# dianji.net
KiCad netlist of a schematic drawn in Altium Designer
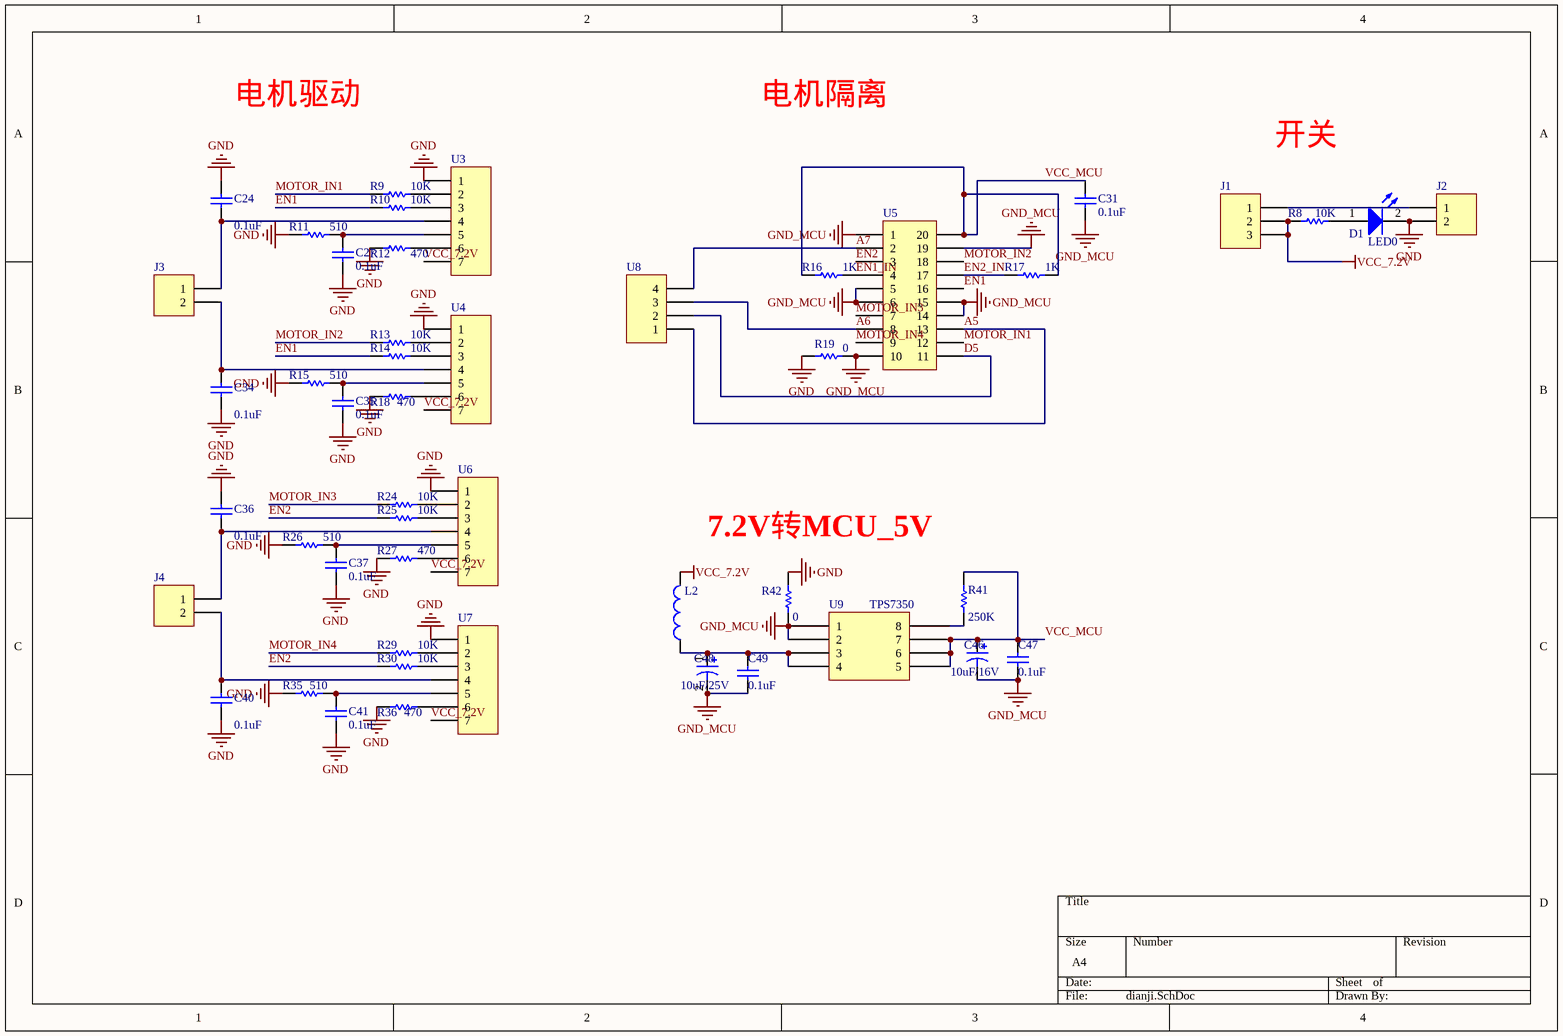
[diagram p0: dianji.SchDoc]

(export (version "E")
  (design (tool "Eeschema 10.0.6"))
  (components
    (comp (ref "C24")
      (value "0.1uF")
      (footprint "C0805")
      (description "Capacitor")
      (fields (field (name "PUBLISHER") "Altium Limited"))
      (libsource (lib "Miscellaneous Devices") (part "Cap"))
    )
    (comp (ref "C27")
      (value "0.1uF")
      (footprint "C0805")
      (description "Capacitor")
      (fields (field (name "PUBLISHER") "Altium Limited"))
      (libsource (lib "Miscellaneous Devices") (part "Cap"))
    )
    (comp (ref "C31")
      (value "0.1uF")
      (footprint "C0805")
      (description "Capacitor")
      (fields (field (name "PUBLISHER") "Altium Limited"))
      (libsource (lib "Miscellaneous Devices") (part "Cap"))
    )
    (comp (ref "C34")
      (value "0.1uF")
      (footprint "C0805")
      (description "Capacitor")
      (fields (field (name "PUBLISHER") "Altium Limited"))
      (libsource (lib "Miscellaneous Devices") (part "Cap"))
    )
    (comp (ref "C35")
      (value "0.1uF")
      (footprint "C0805")
      (description "Capacitor")
      (fields (field (name "PUBLISHER") "Altium Limited"))
      (libsource (lib "Miscellaneous Devices") (part "Cap"))
    )
    (comp (ref "C36")
      (value "0.1uF")
      (footprint "C0805")
      (description "Capacitor")
      (fields (field (name "PUBLISHER") "Altium Limited"))
      (libsource (lib "Miscellaneous Devices") (part "Cap"))
    )
    (comp (ref "C37")
      (value "0.1uF")
      (footprint "C0805")
      (description "Capacitor")
      (fields (field (name "PUBLISHER") "Altium Limited"))
      (libsource (lib "Miscellaneous Devices") (part "Cap"))
    )
    (comp (ref "C40")
      (value "0.1uF")
      (footprint "C0805")
      (description "Capacitor")
      (fields (field (name "PUBLISHER") "Altium Limited"))
      (libsource (lib "Miscellaneous Devices") (part "Cap"))
    )
    (comp (ref "C41")
      (value "0.1uF")
      (footprint "C0805")
      (description "Capacitor")
      (fields (field (name "PUBLISHER") "Altium Limited"))
      (libsource (lib "Miscellaneous Devices") (part "Cap"))
    )
    (comp (ref "C46")
      (value "10uF/16V")
      (footprint "C1206")
      (description "Polarized Capacitor (Radial)")
      (fields (field (name "PUBLISHER") "Altium Limited"))
      (libsource (lib "Miscellaneous Devices") (part "Cap Pol1"))
    )
    (comp (ref "C47")
      (value "0.1uF")
      (footprint "C0805")
      (description "Capacitor")
      (fields (field (name "PUBLISHER") "Altium Limited"))
      (libsource (lib "Miscellaneous Devices") (part "Cap"))
    )
    (comp (ref "C48")
      (value "10uF/25V")
      (footprint "C1206")
      (description "Polarized Capacitor (Radial)")
      (fields (field (name "PUBLISHER") "Altium Limited"))
      (libsource (lib "") (part "Cap Pol1_1"))
    )
    (comp (ref "C49")
      (value "0.1uF")
      (footprint "C0805")
      (description "Capacitor")
      (fields (field (name "PUBLISHER") "Altium Limited"))
      (libsource (lib "Miscellaneous Devices") (part "Cap"))
    )
    (comp (ref "D1")
      (value "LED0")
      (footprint "d0603")
      (description "Typical INFRARED GaAs LED")
      (fields (field (name "PUBLISHER") "Altium Limited"))
      (libsource (lib "Miscellaneous Devices") (part "LED0"))
    )
    (comp (ref "J1")
      (value "Header 3")
      (footprint "7.2")
      (description "Header, 3-Pin")
      (fields (field (name "PUBLISHER") "Altium Limited"))
      (libsource (lib "Miscellaneous Connectors") (part "Header 3"))
    )
    (comp (ref "J2")
      (value "Header 2")
      (footprint "PCBComponent_1 - duplicate5")
      (description "Header, 2-Pin")
      (fields (field (name "PUBLISHER") "Altium Limited"))
      (libsource (lib "") (part "Header 2_1"))
    )
    (comp (ref "J3")
      (value "Header 2")
      (footprint "1")
      (description "Header, 2-Pin")
      (fields (field (name "PUBLISHER") "Altium Limited"))
      (libsource (lib "Miscellaneous Connectors") (part "Header 2"))
    )
    (comp (ref "J4")
      (value "Header 2")
      (footprint "1")
      (description "Header, 2-Pin")
      (fields (field (name "PUBLISHER") "Altium Limited"))
      (libsource (lib "Miscellaneous Connectors") (part "Header 2"))
    )
    (comp (ref "L2")
      (value "~")
      (footprint "L0805")
      (description "Inductor")
      (fields (field (name "PUBLISHER") "Altium Limited"))
      (libsource (lib "Miscellaneous Devices") (part "Inductor"))
    )
    (comp (ref "R8")
      (value "10K")
      (footprint "R0805")
      (description "Resistor")
      (fields (field (name "Comment") "Res1") (field (name "PUBLISHER") "Altium Limited"))
      (libsource (lib "Miscellaneous Devices") (part "Res1"))
    )
    (comp (ref "R9")
      (value "10K")
      (footprint "R0805")
      (description "Resistor")
      (fields (field (name "PUBLISHER") "Altium Limited"))
      (libsource (lib "Miscellaneous Devices") (part "Res1"))
    )
    (comp (ref "R10")
      (value "10K")
      (footprint "R0805")
      (description "Resistor")
      (fields (field (name "PUBLISHER") "Altium Limited"))
      (libsource (lib "Miscellaneous Devices") (part "Res1"))
    )
    (comp (ref "R11")
      (value "510")
      (footprint "R0805")
      (description "Resistor")
      (fields (field (name "Comment") "510R") (field (name "PUBLISHER") "Altium Limited"))
      (libsource (lib "Miscellaneous Devices") (part "Res1"))
    )
    (comp (ref "R12")
      (value "470")
      (footprint "R0805")
      (description "Resistor")
      (fields (field (name "Comment") "470R") (field (name "PUBLISHER") "Altium Limited"))
      (libsource (lib "Miscellaneous Devices") (part "Res1"))
    )
    (comp (ref "R13")
      (value "10K")
      (footprint "R0805")
      (description "Resistor")
      (fields (field (name "PUBLISHER") "Altium Limited"))
      (libsource (lib "Miscellaneous Devices") (part "Res1"))
    )
    (comp (ref "R14")
      (value "10K")
      (footprint "R0805")
      (description "Resistor")
      (fields (field (name "Comment") "Res1") (field (name "PUBLISHER") "Altium Limited"))
      (libsource (lib "Miscellaneous Devices") (part "Res1"))
    )
    (comp (ref "R15")
      (value "510")
      (footprint "R0805")
      (description "Resistor")
      (fields (field (name "Comment") "510R") (field (name "PUBLISHER") "Altium Limited"))
      (libsource (lib "Miscellaneous Devices") (part "Res1"))
    )
    (comp (ref "R16")
      (value "1K")
      (footprint "R0805")
      (description "Resistor")
      (fields (field (name "PUBLISHER") "Altium Limited"))
      (libsource (lib "Miscellaneous Devices") (part "Res1"))
    )
    (comp (ref "R17")
      (value "1K")
      (footprint "R0805")
      (description "Resistor")
      (fields (field (name "PUBLISHER") "Altium Limited"))
      (libsource (lib "Miscellaneous Devices") (part "Res1"))
    )
    (comp (ref "R18")
      (value "470")
      (footprint "R0805")
      (description "Resistor")
      (fields (field (name "Comment") "470R") (field (name "PUBLISHER") "Altium Limited"))
      (libsource (lib "Miscellaneous Devices") (part "Res1"))
    )
    (comp (ref "R19")
      (value "0")
      (footprint "R0805")
      (description "Resistor")
      (fields (field (name "PUBLISHER") "Altium Limited"))
      (libsource (lib "Miscellaneous Devices") (part "Res1"))
    )
    (comp (ref "R24")
      (value "10K")
      (footprint "R0805")
      (description "Resistor")
      (fields (field (name "PUBLISHER") "Altium Limited"))
      (libsource (lib "Miscellaneous Devices") (part "Res1"))
    )
    (comp (ref "R25")
      (value "10K")
      (footprint "R0805")
      (description "Resistor")
      (fields (field (name "PUBLISHER") "Altium Limited"))
      (libsource (lib "Miscellaneous Devices") (part "Res1"))
    )
    (comp (ref "R26")
      (value "510")
      (footprint "R0805")
      (description "Resistor")
      (fields (field (name "Comment") "510R") (field (name "PUBLISHER") "Altium Limited"))
      (libsource (lib "Miscellaneous Devices") (part "Res1"))
    )
    (comp (ref "R27")
      (value "470")
      (footprint "R0805")
      (description "Resistor")
      (fields (field (name "Comment") "470R") (field (name "PUBLISHER") "Altium Limited"))
      (libsource (lib "Miscellaneous Devices") (part "Res1"))
    )
    (comp (ref "R29")
      (value "10K")
      (footprint "R0805")
      (description "Resistor")
      (fields (field (name "PUBLISHER") "Altium Limited"))
      (libsource (lib "Miscellaneous Devices") (part "Res1"))
    )
    (comp (ref "R30")
      (value "10K")
      (footprint "R0805")
      (description "Resistor")
      (fields (field (name "PUBLISHER") "Altium Limited"))
      (libsource (lib "Miscellaneous Devices") (part "Res1"))
    )
    (comp (ref "R35")
      (value "510")
      (footprint "R0805")
      (description "Resistor")
      (fields (field (name "Comment") "510R") (field (name "PUBLISHER") "Altium Limited"))
      (libsource (lib "Miscellaneous Devices") (part "Res1"))
    )
    (comp (ref "R36")
      (value "470")
      (footprint "R0805")
      (description "Resistor")
      (fields (field (name "Comment") "470R") (field (name "PUBLISHER") "Altium Limited"))
      (libsource (lib "Miscellaneous Devices") (part "Res1"))
    )
    (comp (ref "R41")
      (value "250K")
      (footprint "R0805")
      (description "Resistor")
      (fields (field (name "PUBLISHER") "Altium Limited"))
      (libsource (lib "Miscellaneous Devices") (part "Res1"))
    )
    (comp (ref "R42")
      (value "0")
      (footprint "R0805")
      (description "Resistor")
      (fields (field (name "PUBLISHER") "Altium Limited"))
      (libsource (lib "Miscellaneous Devices") (part "Res1"))
    )
    (comp (ref "U3")
      (value "Header 7")
      (footprint "BST7970")
      (description "Header, 7-Pin")
      (fields (field (name "PUBLISHER") "Altium Limited"))
      (libsource (lib "Miscellaneous Connectors") (part "Header 7"))
    )
    (comp (ref "U4")
      (value "Header 7")
      (footprint "BST7970")
      (description "Header, 7-Pin")
      (fields (field (name "PUBLISHER") "Altium Limited"))
      (libsource (lib "Miscellaneous Connectors") (part "Header 7"))
    )
    (comp (ref "U5")
      (value "Header 10X2")
      (footprint "xin")
      (description "Header, 10-Pin, Dual row")
      (fields (field (name "PUBLISHER") "Altium Limited"))
      (libsource (lib "Miscellaneous Connectors") (part "Header 10X2"))
    )
    (comp (ref "U6")
      (value "Header 7")
      (footprint "BST7970")
      (description "Header, 7-Pin")
      (fields (field (name "PUBLISHER") "Altium Limited"))
      (libsource (lib "Miscellaneous Connectors") (part "Header 7"))
    )
    (comp (ref "U7")
      (value "Header 7")
      (footprint "BST7970")
      (description "Header, 7-Pin")
      (fields (field (name "PUBLISHER") "Altium Limited"))
      (libsource (lib "Miscellaneous Connectors") (part "Header 7"))
    )
    (comp (ref "U8")
      (value "Header 4")
      (footprint "SIP4")
      (description "Header, 4-Pin")
      (fields (field (name "PUBLISHER") "Altium Limited"))
      (libsource (lib "Miscellaneous Connectors") (part "Header 4"))
    )
    (comp (ref "U9") (value "TPS7350") (footprint "sop8") (libsource (lib "Schlib1") (part "Component_1")))
  )
  (nets
    (net (code "1") (name "/A5") (class "Default")
      (node (ref "U5") (pin "13") (pinfunction "13_13") (pintype "passive"))
      (node (ref "U8") (pin "1") (pinfunction "1_1") (pintype "passive"))
    )
    (net (code "2") (name "/A6") (class "Default")
      (node (ref "U5") (pin "8") (pinfunction "8_8") (pintype "passive"))
      (node (ref "U8") (pin "3") (pinfunction "3_3") (pintype "passive"))
    )
    (net (code "3") (name "/A7") (class "Default")
      (node (ref "U5") (pin "2") (pinfunction "2_2") (pintype "passive"))
      (node (ref "U8") (pin "4") (pinfunction "4_4") (pintype "passive"))
    )
    (net (code "4") (name "/D5") (class "Default")
      (node (ref "U5") (pin "11") (pinfunction "11_11") (pintype "passive"))
      (node (ref "U8") (pin "2") (pinfunction "2_2") (pintype "passive"))
    )
    (net (code "5") (name "/EN1") (class "Default")
      (node (ref "R10") (pin "1") (pinfunction "1_1") (pintype "passive"))
      (node (ref "R14") (pin "1") (pinfunction "1_1") (pintype "passive"))
      (node (ref "U5") (pin "16") (pinfunction "16_16") (pintype "passive"))
    )
    (net (code "6") (name "/EN1_IN") (class "Default")
      (node (ref "R16") (pin "1") (pinfunction "1_1") (pintype "passive"))
      (node (ref "U5") (pin "4") (pinfunction "4_4") (pintype "passive"))
    )
    (net (code "7") (name "/EN2") (class "Default")
      (node (ref "R25") (pin "1") (pinfunction "1_1") (pintype "passive"))
      (node (ref "R30") (pin "1") (pinfunction "1_1") (pintype "passive"))
      (node (ref "U5") (pin "3") (pinfunction "3_3") (pintype "passive"))
    )
    (net (code "8") (name "/EN2_IN") (class "Default")
      (node (ref "R17") (pin "2") (pinfunction "2_2") (pintype "passive"))
      (node (ref "U5") (pin "17") (pinfunction "17_17") (pintype "passive"))
    )
    (net (code "9") (name "/MOTOR_IN1") (class "Default")
      (node (ref "R9") (pin "1") (pinfunction "1_1") (pintype "passive"))
      (node (ref "U5") (pin "12") (pinfunction "12_12") (pintype "passive"))
    )
    (net (code "10") (name "/MOTOR_IN2") (class "Default")
      (node (ref "R13") (pin "1") (pinfunction "1_1") (pintype "passive"))
      (node (ref "U5") (pin "18") (pinfunction "18_18") (pintype "passive"))
    )
    (net (code "11") (name "/MOTOR_IN3") (class "Default")
      (node (ref "R24") (pin "1") (pinfunction "1_1") (pintype "passive"))
      (node (ref "U5") (pin "7") (pinfunction "7_7") (pintype "passive"))
    )
    (net (code "12") (name "/MOTOR_IN4") (class "Default")
      (node (ref "R29") (pin "1") (pinfunction "1_1") (pintype "passive"))
      (node (ref "U5") (pin "9") (pinfunction "9_9") (pintype "passive"))
    )
    (net (code "13") (name "/VCC_MCU") (class "Default")
      (node (ref "C31") (pin "2") (pinfunction "2_2") (pintype "passive"))
      (node (ref "C46") (pin "1") (pinfunction "1_1") (pintype "passive"))
      (node (ref "C47") (pin "2") (pinfunction "2_2") (pintype "passive"))
      (node (ref "R16") (pin "2") (pinfunction "2_2") (pintype "passive"))
      (node (ref "R17") (pin "1") (pinfunction "1_1") (pintype "passive"))
      (node (ref "R41") (pin "2") (pinfunction "2_2") (pintype "passive"))
      (node (ref "U5") (pin "20") (pinfunction "20_20") (pintype "passive"))
      (node (ref "U9") (pin "5") (pinfunction "5_5") (pintype "passive"))
      (node (ref "U9") (pin "6") (pinfunction "6_6") (pintype "passive"))
      (node (ref "U9") (pin "7") (pinfunction "7_7") (pintype "passive"))
    )
    (net (code "14") (name "GND") (class "Default")
      (node (ref "C24") (pin "2") (pinfunction "2_2") (pintype "passive"))
      (node (ref "C27") (pin "1") (pinfunction "1_1") (pintype "passive"))
      (node (ref "C34") (pin "1") (pinfunction "1_1") (pintype "passive"))
      (node (ref "C35") (pin "1") (pinfunction "1_1") (pintype "passive"))
      (node (ref "C36") (pin "2") (pinfunction "2_2") (pintype "passive"))
      (node (ref "C37") (pin "1") (pinfunction "1_1") (pintype "passive"))
      (node (ref "C40") (pin "1") (pinfunction "1_1") (pintype "passive"))
      (node (ref "C41") (pin "1") (pinfunction "1_1") (pintype "passive"))
      (node (ref "D1") (pin "2") (pinfunction "K_2") (pintype "passive"))
      (node (ref "J2") (pin "2") (pinfunction "2_2") (pintype "passive"))
      (node (ref "R11") (pin "1") (pinfunction "1_1") (pintype "passive"))
      (node (ref "R12") (pin "1") (pinfunction "1_1") (pintype "passive"))
      (node (ref "R15") (pin "1") (pinfunction "1_1") (pintype "passive"))
      (node (ref "R18") (pin "1") (pinfunction "1_1") (pintype "passive"))
      (node (ref "R19") (pin "1") (pinfunction "1_1") (pintype "passive"))
      (node (ref "R26") (pin "1") (pinfunction "1_1") (pintype "passive"))
      (node (ref "R27") (pin "1") (pinfunction "1_1") (pintype "passive"))
      (node (ref "R35") (pin "1") (pinfunction "1_1") (pintype "passive"))
      (node (ref "R36") (pin "1") (pinfunction "1_1") (pintype "passive"))
      (node (ref "R42") (pin "2") (pinfunction "2_2") (pintype "passive"))
      (node (ref "U3") (pin "1") (pinfunction "1_1") (pintype "passive"))
      (node (ref "U4") (pin "1") (pinfunction "1_1") (pintype "passive"))
      (node (ref "U6") (pin "1") (pinfunction "1_1") (pintype "passive"))
      (node (ref "U7") (pin "1") (pinfunction "1_1") (pintype "passive"))
    )
    (net (code "15") (name "GND_MCU") (class "Default")
      (node (ref "C31") (pin "1") (pinfunction "1_1") (pintype "passive"))
      (node (ref "C46") (pin "2") (pinfunction "2_2") (pintype "passive"))
      (node (ref "C47") (pin "1") (pinfunction "1_1") (pintype "passive"))
      (node (ref "C48") (pin "2") (pinfunction "2_2") (pintype "passive"))
      (node (ref "C49") (pin "1") (pinfunction "1_1") (pintype "passive"))
      (node (ref "R19") (pin "2") (pinfunction "2_2") (pintype "passive"))
      (node (ref "R42") (pin "1") (pinfunction "1_1") (pintype "passive"))
      (node (ref "U5") (pin "1") (pinfunction "1_1") (pintype "passive"))
      (node (ref "U5") (pin "10") (pinfunction "10_10") (pintype "passive"))
      (node (ref "U5") (pin "14") (pinfunction "14_14") (pintype "passive"))
      (node (ref "U5") (pin "15") (pinfunction "15_15") (pintype "passive"))
      (node (ref "U5") (pin "19") (pinfunction "19_19") (pintype "passive"))
      (node (ref "U5") (pin "5") (pinfunction "5_5") (pintype "passive"))
      (node (ref "U5") (pin "6") (pinfunction "6_6") (pintype "passive"))
      (node (ref "U9") (pin "1") (pinfunction "1_1") (pintype "passive"))
      (node (ref "U9") (pin "2") (pinfunction "2_2") (pintype "passive"))
    )
    (net (code "16") (name "Net-(C24-Pad1)") (class "Default")
      (node (ref "C24") (pin "1") (pinfunction "1_1") (pintype "passive"))
      (node (ref "J3") (pin "1") (pinfunction "1_1") (pintype "passive"))
      (node (ref "U3") (pin "4") (pinfunction "4_4") (pintype "passive"))
    )
    (net (code "17") (name "Net-(C27-Pad2)") (class "Default")
      (node (ref "C27") (pin "2") (pinfunction "2_2") (pintype "passive"))
      (node (ref "R11") (pin "2") (pinfunction "2_2") (pintype "passive"))
      (node (ref "U3") (pin "5") (pinfunction "5_5") (pintype "passive"))
    )
    (net (code "18") (name "Net-(C34-Pad2)") (class "Default")
      (node (ref "C34") (pin "2") (pinfunction "2_2") (pintype "passive"))
      (node (ref "J3") (pin "2") (pinfunction "2_2") (pintype "passive"))
      (node (ref "U4") (pin "4") (pinfunction "4_4") (pintype "passive"))
    )
    (net (code "19") (name "Net-(C35-Pad2)") (class "Default")
      (node (ref "C35") (pin "2") (pinfunction "2_2") (pintype "passive"))
      (node (ref "R15") (pin "2") (pinfunction "2_2") (pintype "passive"))
      (node (ref "U4") (pin "5") (pinfunction "5_5") (pintype "passive"))
    )
    (net (code "20") (name "Net-(C36-Pad1)") (class "Default")
      (node (ref "C36") (pin "1") (pinfunction "1_1") (pintype "passive"))
      (node (ref "J4") (pin "1") (pinfunction "1_1") (pintype "passive"))
      (node (ref "U6") (pin "4") (pinfunction "4_4") (pintype "passive"))
    )
    (net (code "21") (name "Net-(C37-Pad2)") (class "Default")
      (node (ref "C37") (pin "2") (pinfunction "2_2") (pintype "passive"))
      (node (ref "R26") (pin "2") (pinfunction "2_2") (pintype "passive"))
      (node (ref "U6") (pin "5") (pinfunction "5_5") (pintype "passive"))
    )
    (net (code "22") (name "Net-(C40-Pad2)") (class "Default")
      (node (ref "C40") (pin "2") (pinfunction "2_2") (pintype "passive"))
      (node (ref "J4") (pin "2") (pinfunction "2_2") (pintype "passive"))
      (node (ref "U7") (pin "4") (pinfunction "4_4") (pintype "passive"))
    )
    (net (code "23") (name "Net-(C41-Pad2)") (class "Default")
      (node (ref "C41") (pin "2") (pinfunction "2_2") (pintype "passive"))
      (node (ref "R35") (pin "2") (pinfunction "2_2") (pintype "passive"))
      (node (ref "U7") (pin "5") (pinfunction "5_5") (pintype "passive"))
    )
    (net (code "24") (name "Net-(C48-Pad1)") (class "Default")
      (node (ref "C48") (pin "1") (pinfunction "1_1") (pintype "passive"))
      (node (ref "C49") (pin "2") (pinfunction "2_2") (pintype "passive"))
      (node (ref "L2") (pin "1") (pinfunction "1_1") (pintype "passive"))
      (node (ref "U9") (pin "3") (pinfunction "3_3") (pintype "passive"))
      (node (ref "U9") (pin "4") (pinfunction "4_4") (pintype "passive"))
    )
    (net (code "25") (name "Net-(D1-A)") (class "Default")
      (node (ref "D1") (pin "1") (pinfunction "A_1") (pintype "passive"))
      (node (ref "R8") (pin "2") (pinfunction "2_2") (pintype "passive"))
    )
    (net (code "26") (name "Net-(J1-Pad1)") (class "Default")
      (node (ref "J1") (pin "1") (pinfunction "1_1") (pintype "passive"))
      (node (ref "J2") (pin "1") (pinfunction "1_1") (pintype "passive"))
    )
    (net (code "27") (name "Net-(R9-Pad2)") (class "Default")
      (node (ref "R9") (pin "2") (pinfunction "2_2") (pintype "passive"))
      (node (ref "U3") (pin "2") (pinfunction "2_2") (pintype "passive"))
    )
    (net (code "28") (name "Net-(R10-Pad2)") (class "Default")
      (node (ref "R10") (pin "2") (pinfunction "2_2") (pintype "passive"))
      (node (ref "U3") (pin "3") (pinfunction "3_3") (pintype "passive"))
    )
    (net (code "29") (name "Net-(R12-Pad2)") (class "Default")
      (node (ref "R12") (pin "2") (pinfunction "2_2") (pintype "passive"))
      (node (ref "U3") (pin "6") (pinfunction "6_6") (pintype "passive"))
    )
    (net (code "30") (name "Net-(R13-Pad2)") (class "Default")
      (node (ref "R13") (pin "2") (pinfunction "2_2") (pintype "passive"))
      (node (ref "U4") (pin "2") (pinfunction "2_2") (pintype "passive"))
    )
    (net (code "31") (name "Net-(R14-Pad2)") (class "Default")
      (node (ref "R14") (pin "2") (pinfunction "2_2") (pintype "passive"))
      (node (ref "U4") (pin "3") (pinfunction "3_3") (pintype "passive"))
    )
    (net (code "32") (name "Net-(R18-Pad2)") (class "Default")
      (node (ref "R18") (pin "2") (pinfunction "2_2") (pintype "passive"))
      (node (ref "U4") (pin "6") (pinfunction "6_6") (pintype "passive"))
    )
    (net (code "33") (name "Net-(R24-Pad2)") (class "Default")
      (node (ref "R24") (pin "2") (pinfunction "2_2") (pintype "passive"))
      (node (ref "U6") (pin "2") (pinfunction "2_2") (pintype "passive"))
    )
    (net (code "34") (name "Net-(R25-Pad2)") (class "Default")
      (node (ref "R25") (pin "2") (pinfunction "2_2") (pintype "passive"))
      (node (ref "U6") (pin "3") (pinfunction "3_3") (pintype "passive"))
    )
    (net (code "35") (name "Net-(R27-Pad2)") (class "Default")
      (node (ref "R27") (pin "2") (pinfunction "2_2") (pintype "passive"))
      (node (ref "U6") (pin "6") (pinfunction "6_6") (pintype "passive"))
    )
    (net (code "36") (name "Net-(R29-Pad2)") (class "Default")
      (node (ref "R29") (pin "2") (pinfunction "2_2") (pintype "passive"))
      (node (ref "U7") (pin "2") (pinfunction "2_2") (pintype "passive"))
    )
    (net (code "37") (name "Net-(R30-Pad2)") (class "Default")
      (node (ref "R30") (pin "2") (pinfunction "2_2") (pintype "passive"))
      (node (ref "U7") (pin "3") (pinfunction "3_3") (pintype "passive"))
    )
    (net (code "38") (name "Net-(R36-Pad2)") (class "Default")
      (node (ref "R36") (pin "2") (pinfunction "2_2") (pintype "passive"))
      (node (ref "U7") (pin "6") (pinfunction "6_6") (pintype "passive"))
    )
    (net (code "39") (name "Net-(R41-Pad1)") (class "Default")
      (node (ref "R41") (pin "1") (pinfunction "1_1") (pintype "passive"))
      (node (ref "U9") (pin "8") (pinfunction "8_8") (pintype "passive"))
    )
    (net (code "40") (name "VCC_7.2V") (class "Default")
      (node (ref "J1") (pin "2") (pinfunction "2_2") (pintype "passive"))
      (node (ref "J1") (pin "3") (pinfunction "3_3") (pintype "passive"))
      (node (ref "L2") (pin "2") (pinfunction "2_2") (pintype "passive"))
      (node (ref "R8") (pin "1") (pinfunction "1_1") (pintype "passive"))
      (node (ref "U3") (pin "7") (pinfunction "7_7") (pintype "passive"))
      (node (ref "U4") (pin "7") (pinfunction "7_7") (pintype "passive"))
      (node (ref "U6") (pin "7") (pinfunction "7_7") (pintype "passive"))
      (node (ref "U7") (pin "7") (pinfunction "7_7") (pintype "passive"))
    )
  )
)
